# Elreg_Sender_Top.net
KiCad netlist of a schematic drawn in Altium Designer
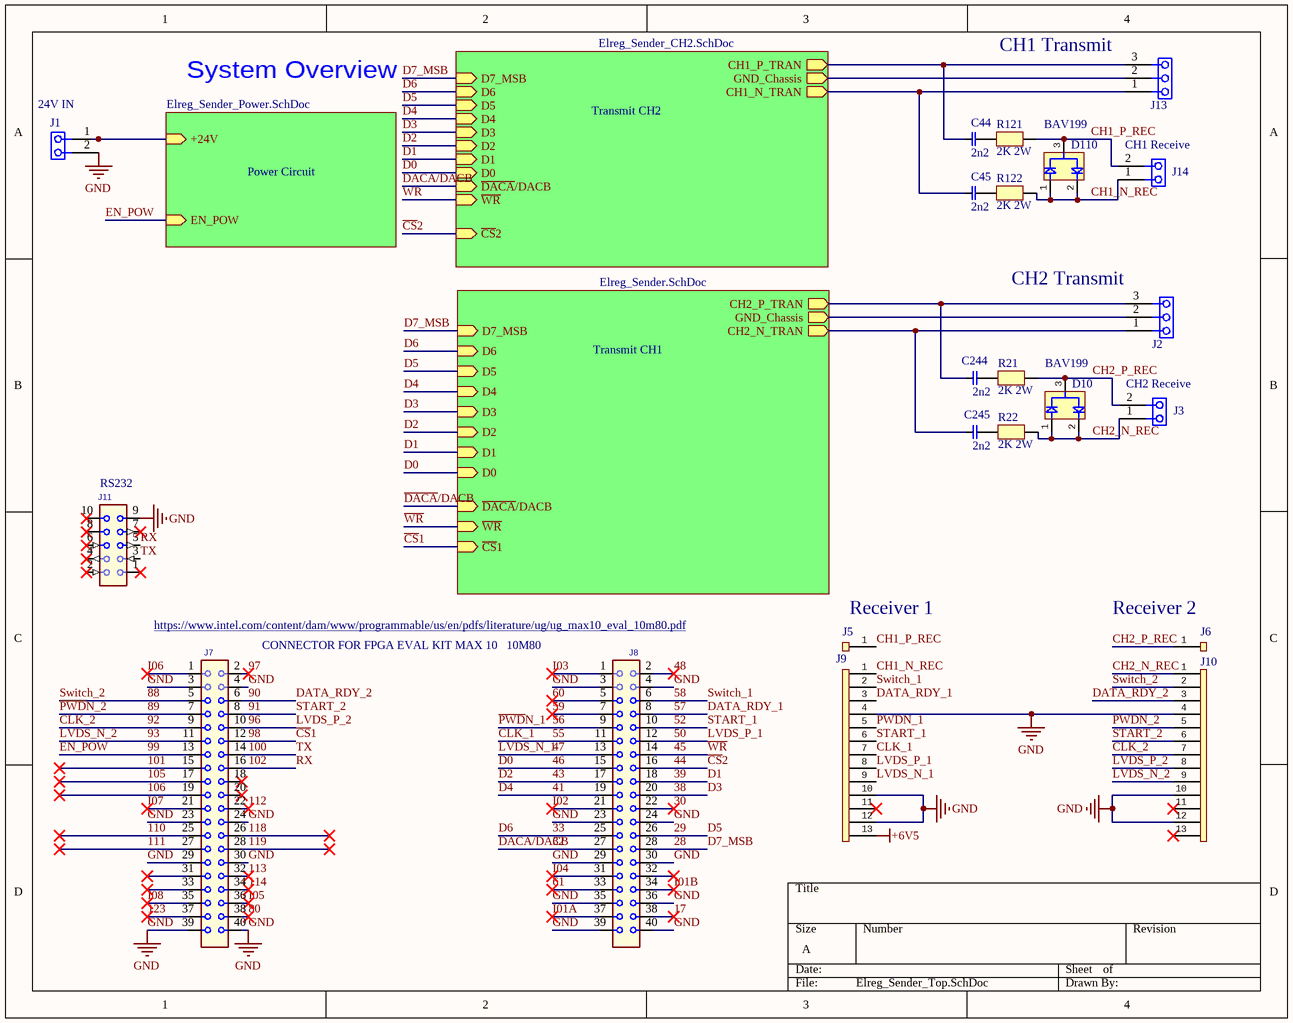
[diagram p0: Elreg_Sender_Top.SchDoc]

(export (version "E")
  (design (tool "Eeschema 10.0.6"))
  (components
    (comp (ref "C44")
      (value "2n2")
      (footprint "CAP-1210")
      (fields (field (name "TOLERANCE") "±10%"))
      (libsource (lib "Elreg_Sender") (part "C-1210"))
    )
    (comp (ref "C45")
      (value "2n2")
      (footprint "CAP-1210")
      (fields (field (name "TOLERANCE") "±10%"))
      (libsource (lib "Elreg_Sender") (part "C-1210"))
    )
    (comp (ref "C244")
      (value "2n2")
      (footprint "CAP-1210")
      (fields (field (name "TOLERANCE") "±10%"))
      (libsource (lib "Elreg_Sender") (part "C-1210"))
    )
    (comp (ref "C245")
      (value "2n2")
      (footprint "CAP-1210")
      (fields (field (name "TOLERANCE") "±10%"))
      (libsource (lib "Elreg_Sender") (part "C-1210"))
    )
    (comp (ref "D10") (value "BAV199") (footprint "BAV199") (libsource (lib "Elreg_Sender") (part "BAV199")))
    (comp (ref "D110") (value "BAV199") (footprint "BAV199") (libsource (lib "Elreg_Sender") (part "BAV199")))
    (comp (ref "J1")
      (value "24V IN")
      (footprint "WAGO_2_pins")
      (libsource (lib "Elreg_Sender") (part "2x1 connector"))
    )
    (comp (ref "J2")
      (value "CONN 3x1")
      (footprint "WAGO-3_pins")
      (libsource (lib "Elreg_Sender") (part "3x1 connector"))
    )
    (comp (ref "J3")
      (value "CH2 Receive")
      (footprint "WAGO_2_pins")
      (libsource (lib "Elreg_Sender") (part "2x1 connector"))
    )
    (comp (ref "J5") (value "CON1_b") (footprint "CONN1 _b") (libsource (lib "") (part "CON1_b_1")))
    (comp (ref "J6") (value "CON1_b") (footprint "CONN1 _b") (libsource (lib "Elreg_Sender") (part "CON1_b")))
    (comp (ref "J7")
      (value "Header 2X20")
      (footprint "HEADER_2x20_2_54_1mm")
      (libsource (lib "Elreg_Sender") (part "HEADER_2x20_2.54_1"))
    )
    (comp (ref "J8")
      (value "Header 2X20")
      (footprint "HEADER_2x20_2_54_1mm")
      (libsource (lib "Elreg_Sender") (part "HEADER_2x20_2.54_1"))
    )
    (comp (ref "J9") (value "CON13") (footprint "CONN13") (libsource (lib "") (part "CON13_1")))
    (comp (ref "J10") (value "CON14") (footprint "CONN13") (libsource (lib "Elreg_Sender") (part "CON13")))
    (comp (ref "J11")
      (value "Header 2X5")
      (footprint "PIN-2X5-2.54-1.0")
      (description "Conn Unshrouded Header HDR 10 POS 2.54mm Solder ST Thru-Hole")
      (libsource (lib "Elreg_Sender") (part "HEADER_2x5_2.54"))
    )
    (comp (ref "J13")
      (value "CONN 3x1")
      (footprint "WAGO-3_pins")
      (libsource (lib "Elreg_Sender") (part "3x1 connector"))
    )
    (comp (ref "J14")
      (value "CH1 Receive")
      (footprint "WAGO_2_pins")
      (libsource (lib "Elreg_Sender") (part "2x1 connector"))
    )
    (comp (ref "R21")
      (value "2K 2W")
      (footprint "RES2512")
      (fields (field (name "TOLERANCE") "±1%"))
      (libsource (lib "Elreg_Sender") (part "RES SMD 75K OHM 1% 2W 2512"))
    )
    (comp (ref "R22")
      (value "2K 2W")
      (footprint "RES2512")
      (fields (field (name "TOLERANCE") "±1%"))
      (libsource (lib "Elreg_Sender") (part "RES SMD 75K OHM 1% 2W 2512"))
    )
    (comp (ref "R121")
      (value "2K 2W")
      (footprint "RES2512")
      (fields (field (name "TOLERANCE") "±1%"))
      (libsource (lib "Elreg_Sender") (part "RES SMD 75K OHM 1% 2W 2512"))
    )
    (comp (ref "R122")
      (value "2K 2W")
      (footprint "RES2512")
      (fields (field (name "TOLERANCE") "±1%"))
      (libsource (lib "Elreg_Sender") (part "RES SMD 75K OHM 1% 2W 2512"))
    )
  )
  (nets
    (net (code "1") (name "+6V5") (class "Default")
      (node (ref "J9") (pin "13") (pinfunction "36_13") (pintype "passive"))
    )
    (net (code "2") (name "/+24V") (class "Default")
      (node (ref "J1") (pin "1") (pinfunction "Vout_1") (pintype "passive"))
    )
    (net (code "3") (name "/17") (class "Default")
      (node (ref "J8") (pin "38") (pintype "passive+no_connect"))
    )
    (net (code "4") (name "/28") (class "Default") (node (ref "J8") (pin "28") (pintype "passive")))
    (net (code "5") (name "/29") (class "Default") (node (ref "J8") (pin "26") (pintype "passive")))
    (net (code "6") (name "/30") (class "Default")
      (node (ref "J8") (pin "22") (pintype "passive+no_connect"))
    )
    (net (code "7") (name "/32") (class "Default") (node (ref "J8") (pin "27") (pintype "passive")))
    (net (code "8") (name "/33") (class "Default") (node (ref "J8") (pin "25") (pintype "passive")))
    (net (code "9") (name "/38") (class "Default") (node (ref "J8") (pin "20") (pintype "passive")))
    (net (code "10") (name "/39") (class "Default") (node (ref "J8") (pin "18") (pintype "passive")))
    (net (code "11") (name "/41") (class "Default") (node (ref "J8") (pin "19") (pintype "power_in")))
    (net (code "12") (name "/43") (class "Default") (node (ref "J8") (pin "17") (pintype "passive")))
    (net (code "13") (name "/44") (class "Default") (node (ref "J8") (pin "16") (pintype "passive")))
    (net (code "14") (name "/45") (class "Default") (node (ref "J8") (pin "14") (pintype "passive")))
    (net (code "15") (name "/46") (class "Default") (node (ref "J8") (pin "15") (pintype "passive")))
    (net (code "16") (name "/47") (class "Default")
      (node (ref "J8") (pin "13") (pintype "passive"))
      (node (ref "J9") (pin "9") (pinfunction "32_9") (pintype "passive"))
    )
    (net (code "17") (name "/48") (class "Default")
      (node (ref "J8") (pin "2") (pinfunction "DSR_2") (pintype "passive+no_connect"))
    )
    (net (code "18") (name "/50") (class "Default")
      (node (ref "J8") (pin "12") (pintype "passive"))
      (node (ref "J9") (pin "8") (pinfunction "31_8") (pintype "passive"))
    )
    (net (code "19") (name "/52") (class "Default")
      (node (ref "J8") (pin "10") (pinfunction "10_10") (pintype "passive"))
      (node (ref "J9") (pin "6") (pinfunction "29_6") (pintype "passive"))
    )
    (net (code "20") (name "/55") (class "Default")
      (node (ref "J8") (pin "11") (pinfunction "11_11") (pintype "passive"))
      (node (ref "J9") (pin "7") (pinfunction "30_7") (pintype "passive"))
    )
    (net (code "21") (name "/56") (class "Default")
      (node (ref "J8") (pin "9") (pinfunction "+PWR_9") (pintype "power_in"))
      (node (ref "J9") (pin "5") (pinfunction "28_5") (pintype "passive"))
    )
    (net (code "22") (name "/57") (class "Default")
      (node (ref "J8") (pin "8") (pinfunction "8_8") (pintype "passive"))
      (node (ref "J9") (pin "3") (pinfunction "26_3") (pintype "passive"))
    )
    (net (code "23") (name "/58") (class "Default")
      (node (ref "J8") (pin "6") (pinfunction "CTS_6") (pintype "passive"))
      (node (ref "J9") (pin "2") (pinfunction "25_2") (pintype "passive"))
    )
    (net (code "24") (name "/59") (class "Default")
      (node (ref "J8") (pin "7") (pinfunction "DTR_7") (pintype "passive+no_connect"))
    )
    (net (code "25") (name "/60") (class "Default")
      (node (ref "J8") (pin "5") (pinfunction "TX_5") (pintype "passive+no_connect"))
    )
    (net (code "26") (name "/61") (class "Default")
      (node (ref "J8") (pin "33") (pintype "passive+no_connect"))
    )
    (net (code "27") (name "/80") (class "Default")
      (node (ref "J7") (pin "38") (pintype "passive+no_connect"))
    )
    (net (code "28") (name "/88") (class "Default")
      (node (ref "J10") (pin "2") (pinfunction "25_2") (pintype "passive"))
      (node (ref "J7") (pin "5") (pinfunction "TX_5") (pintype "passive"))
    )
    (net (code "29") (name "/89") (class "Default")
      (node (ref "J10") (pin "5") (pinfunction "28_5") (pintype "passive"))
      (node (ref "J7") (pin "7") (pinfunction "DTR_7") (pintype "passive"))
    )
    (net (code "30") (name "/90") (class "Default")
      (node (ref "J10") (pin "3") (pinfunction "26_3") (pintype "passive"))
      (node (ref "J7") (pin "6") (pinfunction "CTS_6") (pintype "passive"))
    )
    (net (code "31") (name "/91") (class "Default")
      (node (ref "J10") (pin "6") (pinfunction "29_6") (pintype "passive"))
      (node (ref "J7") (pin "8") (pinfunction "8_8") (pintype "passive"))
    )
    (net (code "32") (name "/92") (class "Default")
      (node (ref "J10") (pin "7") (pinfunction "30_7") (pintype "passive"))
      (node (ref "J7") (pin "9") (pinfunction "+PWR_9") (pintype "power_in"))
    )
    (net (code "33") (name "/93") (class "Default")
      (node (ref "J10") (pin "9") (pinfunction "32_9") (pintype "passive"))
      (node (ref "J7") (pin "11") (pinfunction "11_11") (pintype "passive"))
    )
    (net (code "34") (name "/96") (class "Default")
      (node (ref "J10") (pin "8") (pinfunction "31_8") (pintype "passive"))
      (node (ref "J7") (pin "10") (pinfunction "10_10") (pintype "passive"))
    )
    (net (code "35") (name "/97") (class "Default")
      (node (ref "J7") (pin "2") (pinfunction "DSR_2") (pintype "passive+no_connect"))
    )
    (net (code "36") (name "/98") (class "Default") (node (ref "J7") (pin "12") (pintype "passive")))
    (net (code "37") (name "/99") (class "Default") (node (ref "J7") (pin "13") (pintype "passive")))
    (net (code "38") (name "/100") (class "Default")
      (node (ref "J11") (pin "3") (pinfunction "RX_3") (pintype "input"))
      (node (ref "J7") (pin "14") (pintype "passive"))
    )
    (net (code "39") (name "/101") (class "Default")
      (node (ref "J7") (pin "15") (pintype "passive+no_connect"))
    )
    (net (code "40") (name "/102") (class "Default")
      (node (ref "J11") (pin "5") (pinfunction "TX_5") (pintype "output"))
      (node (ref "J7") (pin "16") (pintype "passive"))
    )
    (net (code "41") (name "/105") (class "Default")
      (node (ref "J7") (pin "17") (pintype "passive+no_connect"))
    )
    (net (code "42") (name "/106") (class "Default")
      (node (ref "J7") (pin "19") (pintype "power_in+no_connect"))
    )
    (net (code "43") (name "/110") (class "Default")
      (node (ref "J7") (pin "25") (pintype "passive+no_connect"))
    )
    (net (code "44") (name "/111") (class "Default")
      (node (ref "J7") (pin "27") (pintype "passive+no_connect"))
    )
    (net (code "45") (name "/112") (class "Default")
      (node (ref "J7") (pin "22") (pintype "passive+no_connect"))
    )
    (net (code "46") (name "/113") (class "Default")
      (node (ref "J7") (pin "32") (pintype "passive+no_connect"))
    )
    (net (code "47") (name "/114") (class "Default")
      (node (ref "J7") (pin "34") (pintype "passive+no_connect"))
    )
    (net (code "48") (name "/118") (class "Default")
      (node (ref "J7") (pin "26") (pintype "passive+no_connect"))
    )
    (net (code "49") (name "/119") (class "Default")
      (node (ref "J7") (pin "28") (pintype "passive+no_connect"))
    )
    (net (code "50") (name "/123") (class "Default")
      (node (ref "J7") (pin "37") (pintype "passive+no_connect"))
    )
    (net (code "51") (name "/CH1_N_REC") (class "Default")
      (node (ref "D110") (pin "1") (pinfunction "GND_1") (pintype "passive"))
      (node (ref "D110") (pin "2") (pinfunction "GND_2") (pintype "passive"))
      (node (ref "J14") (pin "1") (pinfunction "Vout_1") (pintype "passive"))
      (node (ref "J9") (pin "1") (pinfunction "24_1") (pintype "passive"))
      (node (ref "R122") (pin "1") (pinfunction "G_1") (pintype "passive"))
    )
    (net (code "52") (name "/CH1_N_TRAN") (class "Default")
      (node (ref "C45") (pin "1") (pinfunction "G_1") (pintype "passive"))
      (node (ref "J13") (pin "1") (pinfunction "Vout_1") (pintype "passive"))
    )
    (net (code "53") (name "/CH1_P_REC") (class "Default")
      (node (ref "D110") (pin "3") (pinfunction "GND_3") (pintype "passive"))
      (node (ref "J14") (pin "2") (pinfunction "Vout_2") (pintype "passive"))
      (node (ref "J5") (pin "1") (pinfunction "23_1") (pintype "passive"))
      (node (ref "R121") (pin "1") (pinfunction "G_1") (pintype "passive"))
    )
    (net (code "54") (name "/CH1_P_TRAN") (class "Default")
      (node (ref "C44") (pin "1") (pinfunction "G_1") (pintype "passive"))
      (node (ref "J13") (pin "3") (pinfunction "Vout_3") (pintype "passive"))
    )
    (net (code "55") (name "/CH2_N_REC") (class "Default")
      (node (ref "D10") (pin "1") (pinfunction "GND_1") (pintype "passive"))
      (node (ref "D10") (pin "2") (pinfunction "GND_2") (pintype "passive"))
      (node (ref "J10") (pin "1") (pinfunction "24_1") (pintype "passive"))
      (node (ref "J3") (pin "1") (pinfunction "Vout_1") (pintype "passive"))
      (node (ref "R22") (pin "1") (pinfunction "G_1") (pintype "passive"))
    )
    (net (code "56") (name "/CH2_N_TRAN") (class "Default")
      (node (ref "C245") (pin "1") (pinfunction "G_1") (pintype "passive"))
      (node (ref "J2") (pin "1") (pinfunction "Vout_1") (pintype "passive"))
    )
    (net (code "57") (name "/CH2_P_REC") (class "Default")
      (node (ref "D10") (pin "3") (pinfunction "GND_3") (pintype "passive"))
      (node (ref "J3") (pin "2") (pinfunction "Vout_2") (pintype "passive"))
      (node (ref "J6") (pin "1") (pinfunction "23_1") (pintype "passive"))
      (node (ref "R21") (pin "1") (pinfunction "G_1") (pintype "passive"))
    )
    (net (code "58") (name "/CH2_P_TRAN") (class "Default")
      (node (ref "C244") (pin "1") (pinfunction "G_1") (pintype "passive"))
      (node (ref "J2") (pin "3") (pinfunction "Vout_3") (pintype "passive"))
    )
    (net (code "59") (name "/GND_Chassis") (class "Default")
      (node (ref "J13") (pin "2") (pinfunction "Vout_2") (pintype "passive"))
    )
    (net (code "60") (name "/GND_Chassis_1") (class "Default")
      (node (ref "J2") (pin "2") (pinfunction "Vout_2") (pintype "passive"))
    )
    (net (code "61") (name "/I01A") (class "Default")
      (node (ref "J8") (pin "37") (pintype "passive+no_connect"))
    )
    (net (code "62") (name "/I01B") (class "Default")
      (node (ref "J8") (pin "34") (pintype "passive+no_connect"))
    )
    (net (code "63") (name "/I02") (class "Default")
      (node (ref "J8") (pin "21") (pintype "passive+no_connect"))
    )
    (net (code "64") (name "/I03") (class "Default")
      (node (ref "J8") (pin "1") (pinfunction "1_1") (pintype "passive+no_connect"))
    )
    (net (code "65") (name "/I04") (class "Default")
      (node (ref "J8") (pin "31") (pintype "passive+no_connect"))
    )
    (net (code "66") (name "/I05") (class "Default")
      (node (ref "J7") (pin "36") (pintype "passive+no_connect"))
    )
    (net (code "67") (name "/I06") (class "Default")
      (node (ref "J7") (pin "1") (pinfunction "1_1") (pintype "passive+no_connect"))
    )
    (net (code "68") (name "/I07") (class "Default")
      (node (ref "J7") (pin "21") (pintype "passive+no_connect"))
    )
    (net (code "69") (name "/I08") (class "Default")
      (node (ref "J7") (pin "35") (pintype "passive+no_connect"))
    )
    (net (code "70") (name "GND") (class "Default")
      (node (ref "J1") (pin "2") (pinfunction "Vout_2") (pintype "passive"))
      (node (ref "J10") (pin "10") (pinfunction "33_10") (pintype "passive"))
      (node (ref "J10") (pin "12") (pinfunction "35_12") (pintype "passive"))
      (node (ref "J10") (pin "4") (pinfunction "27_4") (pintype "passive"))
      (node (ref "J11") (pin "9") (pinfunction "+PWR_9") (pintype "power_in"))
      (node (ref "J7") (pin "23") (pintype "passive"))
      (node (ref "J7") (pin "24") (pintype "passive"))
      (node (ref "J7") (pin "29") (pintype "power_in"))
      (node (ref "J7") (pin "3") (pinfunction "RX_3") (pintype "passive"))
      (node (ref "J7") (pin "30") (pintype "passive"))
      (node (ref "J7") (pin "39") (pintype "passive"))
      (node (ref "J7") (pin "4") (pinfunction "RTS_4") (pintype "passive"))
      (node (ref "J7") (pin "40") (pintype "passive"))
      (node (ref "J8") (pin "23") (pintype "passive"))
      (node (ref "J8") (pin "24") (pintype "passive"))
      (node (ref "J8") (pin "29") (pintype "power_in"))
      (node (ref "J8") (pin "3") (pinfunction "RX_3") (pintype "passive"))
      (node (ref "J8") (pin "30") (pintype "passive"))
      (node (ref "J8") (pin "35") (pintype "passive"))
      (node (ref "J8") (pin "36") (pintype "passive"))
      (node (ref "J8") (pin "39") (pintype "passive"))
      (node (ref "J8") (pin "4") (pinfunction "RTS_4") (pintype "passive"))
      (node (ref "J8") (pin "40") (pintype "passive"))
      (node (ref "J9") (pin "10") (pinfunction "33_10") (pintype "passive"))
      (node (ref "J9") (pin "12") (pinfunction "35_12") (pintype "passive"))
      (node (ref "J9") (pin "4") (pinfunction "27_4") (pintype "passive"))
    )
    (net (code "71") (name "Net-(C44-G-Pad2)") (class "Default")
      (node (ref "C44") (pin "2") (pinfunction "G_2") (pintype "passive"))
      (node (ref "R121") (pin "2") (pinfunction "G_2") (pintype "passive"))
    )
    (net (code "72") (name "Net-(C45-G-Pad2)") (class "Default")
      (node (ref "C45") (pin "2") (pinfunction "G_2") (pintype "passive"))
      (node (ref "R122") (pin "2") (pinfunction "G_2") (pintype "passive"))
    )
    (net (code "73") (name "Net-(C244-G-Pad2)") (class "Default")
      (node (ref "C244") (pin "2") (pinfunction "G_2") (pintype "passive"))
      (node (ref "R21") (pin "2") (pinfunction "G_2") (pintype "passive"))
    )
    (net (code "74") (name "Net-(C245-G-Pad2)") (class "Default")
      (node (ref "C245") (pin "2") (pinfunction "G_2") (pintype "passive"))
      (node (ref "R22") (pin "2") (pinfunction "G_2") (pintype "passive"))
    )
    (net (code "75") (name "unconnected-(J7-Pad18)") (class "Default")
      (node (ref "J7") (pin "18") (pintype "passive+no_connect"))
    )
    (net (code "76") (name "unconnected-(J7-Pad20)") (class "Default")
      (node (ref "J7") (pin "20") (pintype "passive+no_connect"))
    )
    (net (code "77") (name "unconnected-(J7-Pad31)") (class "Default")
      (node (ref "J7") (pin "31") (pintype "passive+no_connect"))
    )
    (net (code "78") (name "unconnected-(J7-Pad33)") (class "Default")
      (node (ref "J7") (pin "33") (pintype "passive+no_connect"))
    )
    (net (code "79") (name "unconnected-(J8-Pad32)") (class "Default")
      (node (ref "J8") (pin "32") (pintype "passive+no_connect"))
    )
    (net (code "80") (name "unconnected-(J9-34-Pad11)") (class "Default")
      (node (ref "J9") (pin "11") (pinfunction "34_11") (pintype "passive+no_connect"))
    )
    (net (code "81") (name "unconnected-(J10-34-Pad11)") (class "Default")
      (node (ref "J10") (pin "11") (pinfunction "34_11") (pintype "passive+no_connect"))
    )
    (net (code "82") (name "unconnected-(J10-36-Pad13)") (class "Default")
      (node (ref "J10") (pin "13") (pinfunction "36_13") (pintype "passive+no_connect"))
    )
    (net (code "83") (name "unconnected-(J11-CTS-Pad6)") (class "Default")
      (node (ref "J11") (pin "6") (pinfunction "CTS_6") (pintype "input+no_connect"))
    )
    (net (code "84") (name "unconnected-(J11-DSR-Pad2)") (class "Default")
      (node (ref "J11") (pin "2") (pinfunction "DSR_2") (pintype "input+no_connect"))
    )
    (net (code "85") (name "unconnected-(J11-DTR-Pad7)") (class "Default")
      (node (ref "J11") (pin "7") (pinfunction "DTR_7") (pintype "output+no_connect"))
    )
    (net (code "86") (name "unconnected-(J11-Pad1)") (class "Default")
      (node (ref "J11") (pin "1") (pinfunction "1_1") (pintype "passive+no_connect"))
    )
    (net (code "87") (name "unconnected-(J11-Pad8)") (class "Default")
      (node (ref "J11") (pin "8") (pinfunction "8_8") (pintype "passive+no_connect"))
    )
    (net (code "88") (name "unconnected-(J11-Pad10)") (class "Default")
      (node (ref "J11") (pin "10") (pinfunction "10_10") (pintype "passive+no_connect"))
    )
    (net (code "89") (name "unconnected-(J11-RTS-Pad4)") (class "Default")
      (node (ref "J11") (pin "4") (pinfunction "RTS_4") (pintype "output+no_connect"))
    )
  )
)
